# working.net
KiCad netlist of a schematic drawn in EAGLE
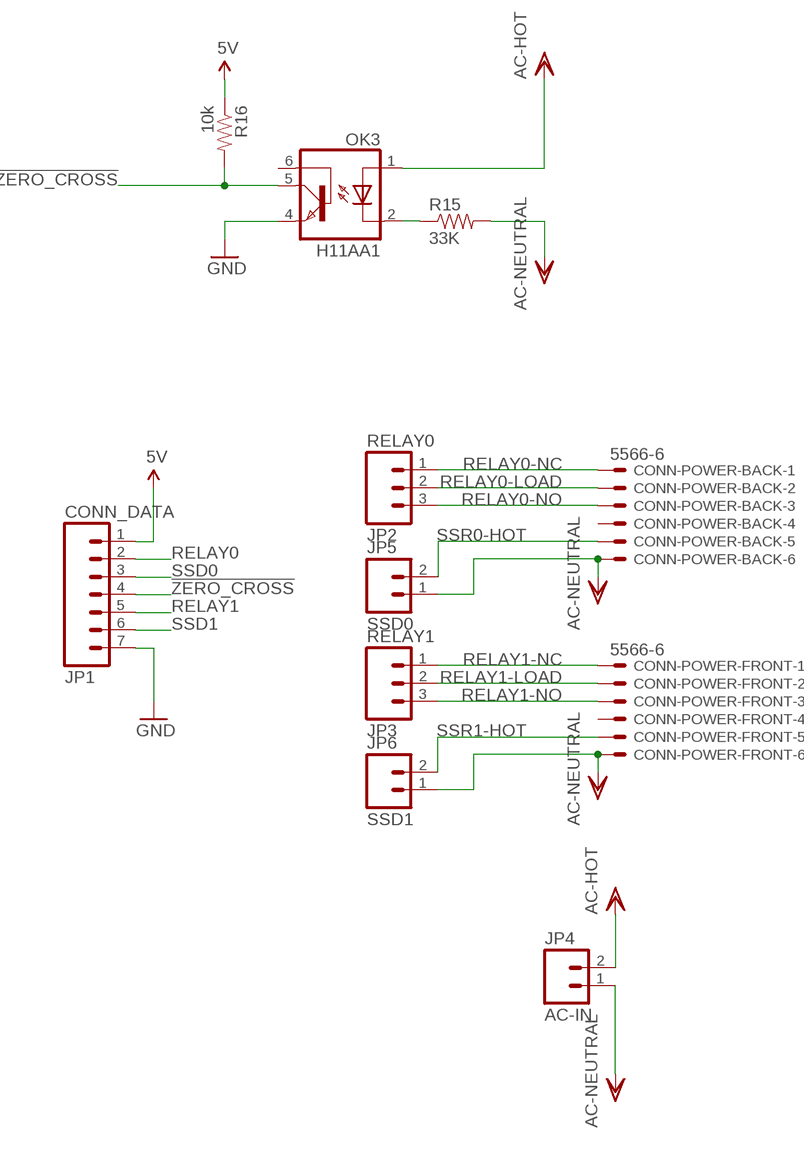
[diagram p0: schematic, sheet 1]
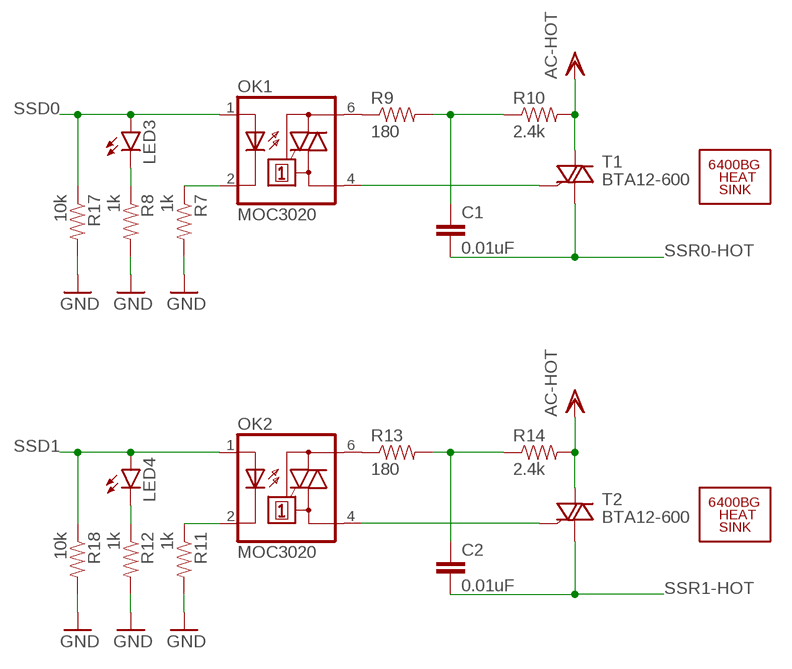
[diagram p1: schematic, sheet 2]
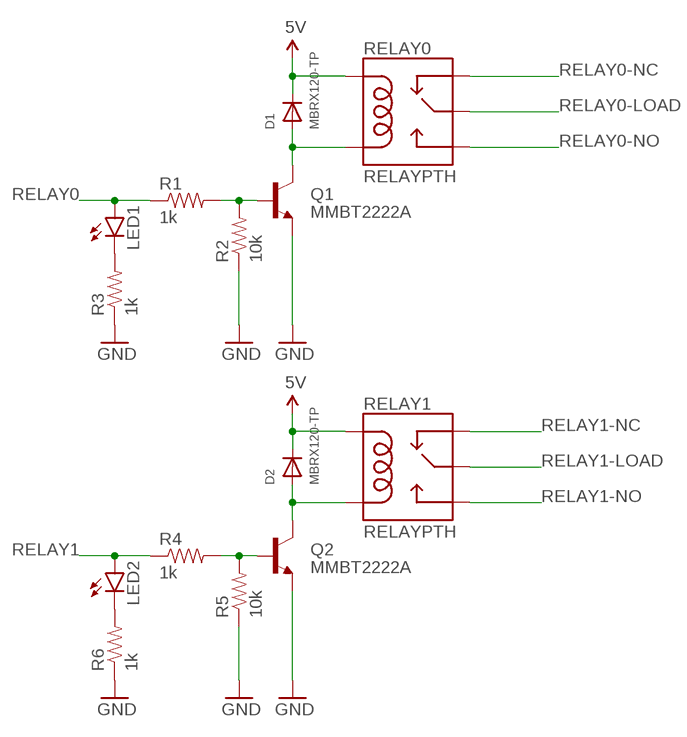
[diagram p2: schematic, sheet 3]

(export (version "E")
  (design (tool "Eeschema 10.0.6"))
  (components
    (comp (ref "D1")
      (value "MBRX120-TP")
      (footprint "eagle-import:SOD-123")
      (libsource (lib "eagle-import") (part "DIODESOD-123"))
    )
    (comp (ref "D2")
      (value "MBRX120-TP")
      (footprint "eagle-import:SOD-123")
      (libsource (lib "eagle-import") (part "DIODESOD-123"))
    )
    (comp (ref "LED1")
      (value "LED0603")
      (footprint "eagle-import:LED-0603")
      (libsource (lib "eagle-import") (part "LED0603"))
    )
    (comp (ref "LED2")
      (value "LED0603")
      (footprint "eagle-import:LED-0603")
      (libsource (lib "eagle-import") (part "LED0603"))
    )
    (comp (ref "Q1")
      (value "MMBT2222A")
      (footprint "eagle-import:SOT23-3")
      (libsource (lib "eagle-import") (part "TRANSISTOR_NPNMMBT2222A"))
    )
    (comp (ref "Q2")
      (value "MMBT2222A")
      (footprint "eagle-import:SOT23-3")
      (libsource (lib "eagle-import") (part "TRANSISTOR_NPNMMBT2222A"))
    )
    (comp (ref "R1")
      (value "1k")
      (footprint "eagle-import:0603-RES")
      (libsource (lib "eagle-import") (part "RESISTOR0603-RES"))
    )
    (comp (ref "R2")
      (value "10k")
      (footprint "eagle-import:0603-RES")
      (libsource (lib "eagle-import") (part "RESISTOR0603-RES"))
    )
    (comp (ref "R3")
      (value "1k")
      (footprint "eagle-import:0603-RES")
      (libsource (lib "eagle-import") (part "RESISTOR0603-RES"))
    )
    (comp (ref "R4")
      (value "1k")
      (footprint "eagle-import:0603-RES")
      (libsource (lib "eagle-import") (part "RESISTOR0603-RES"))
    )
    (comp (ref "R5")
      (value "10k")
      (footprint "eagle-import:0603-RES")
      (libsource (lib "eagle-import") (part "RESISTOR0603-RES"))
    )
    (comp (ref "R6")
      (value "1k")
      (footprint "eagle-import:0603-RES")
      (libsource (lib "eagle-import") (part "RESISTOR0603-RES"))
    )
    (comp (ref "RELAY0")
      (value "RELAYPTH")
      (footprint "eagle-import:RELAY-G5Q")
      (libsource (lib "eagle-import") (part "RELAYPTH"))
    )
    (comp (ref "RELAY1")
      (value "RELAYPTH")
      (footprint "eagle-import:RELAY-G5Q")
      (libsource (lib "eagle-import") (part "RELAYPTH"))
    )
    (comp (ref "CONN-POWER-BACK")
      (value "5566-6")
      (footprint "eagle-import:5566-6")
      (fields (field (name "MPN") "95566-61002"))
      (libsource (lib "eagle-import") (part "5566-6"))
    )
    (comp (ref "CONN-POWER-FRONT")
      (value "5566-6")
      (footprint "eagle-import:5566-6")
      (fields (field (name "MPN") "95566-61002"))
      (libsource (lib "eagle-import") (part "5566-6"))
    )
    (comp (ref "JP1")
      (value "CONN_DATA")
      (footprint "eagle-import:1X07_LONGPADS")
      (libsource (lib "eagle-import") (part "M07LONGPADS"))
    )
    (comp (ref "JP2")
      (value "RELAY0")
      (footprint "eagle-import:SCREWTERMINAL-5MM-3")
      (libsource (lib "eagle-import") (part "M03-SCREW-5MM"))
    )
    (comp (ref "JP3")
      (value "RELAY1")
      (footprint "eagle-import:SCREWTERMINAL-5MM-3")
      (libsource (lib "eagle-import") (part "M03-SCREW-5MM"))
    )
    (comp (ref "JP4")
      (value "AC-IN")
      (footprint "eagle-import:SCREWTERMINAL-5MM-2")
      (libsource (lib "eagle-import") (part "M025MM"))
    )
    (comp (ref "JP5")
      (value "SSD0")
      (footprint "eagle-import:SCREWTERMINAL-5MM-2")
      (libsource (lib "eagle-import") (part "M025MM"))
    )
    (comp (ref "JP6")
      (value "SSD1")
      (footprint "eagle-import:SCREWTERMINAL-5MM-2")
      (libsource (lib "eagle-import") (part "M025MM"))
    )
    (comp (ref "OK3")
      (value "H11AA1")
      (footprint "eagle-import:DIL6-SMD")
      (libsource (lib "eagle-import") (part "H11A?MS1"))
    )
    (comp (ref "R15")
      (value "33K")
      (footprint "eagle-import:0603-RES")
      (libsource (lib "eagle-import") (part "RESISTOR0603-RES"))
    )
    (comp (ref "R16")
      (value "10k")
      (footprint "eagle-import:0603-RES")
      (libsource (lib "eagle-import") (part "RESISTOR0603-RES"))
    )
    (comp (ref "C1")
      (value "0.01uF")
      (footprint "eagle-import:0603-CAP")
      (libsource (lib "eagle-import") (part "CAP0603-CAP"))
    )
    (comp (ref "C2")
      (value "0.01uF")
      (footprint "eagle-import:0603-CAP")
      (libsource (lib "eagle-import") (part "CAP0603-CAP"))
    )
    (comp (ref "LED3")
      (value "LED0603")
      (footprint "eagle-import:LED-0603")
      (libsource (lib "eagle-import") (part "LED0603"))
    )
    (comp (ref "LED4")
      (value "LED0603")
      (footprint "eagle-import:LED-0603")
      (libsource (lib "eagle-import") (part "LED0603"))
    )
    (comp (ref "OK1")
      (value "MOC3020")
      (footprint "eagle-import:DIL6-SMD")
      (fields (field (name "MF") "FAIRCHILD SEMICONDUCTOR") (field (name "MPN") "MOC3031SM"))
      (libsource (lib "eagle-import") (part "MOC30S31"))
    )
    (comp (ref "OK2")
      (value "MOC3020")
      (footprint "eagle-import:DIL6-SMD")
      (fields (field (name "MF") "FAIRCHILD SEMICONDUCTOR") (field (name "MPN") "MOC3031SM"))
      (libsource (lib "eagle-import") (part "MOC30S31"))
    )
    (comp (ref "R7")
      (value "1k")
      (footprint "eagle-import:0603-RES")
      (libsource (lib "eagle-import") (part "RESISTOR0603-RES"))
    )
    (comp (ref "R8")
      (value "1k")
      (footprint "eagle-import:0603-RES")
      (libsource (lib "eagle-import") (part "RESISTOR0603-RES"))
    )
    (comp (ref "R9")
      (value "180")
      (footprint "eagle-import:0603-RES")
      (libsource (lib "eagle-import") (part "RESISTOR0603-RES"))
    )
    (comp (ref "R10")
      (value "2.4k")
      (footprint "eagle-import:0603-RES")
      (libsource (lib "eagle-import") (part "RESISTOR0603-RES"))
    )
    (comp (ref "R11")
      (value "1k")
      (footprint "eagle-import:0603-RES")
      (libsource (lib "eagle-import") (part "RESISTOR0603-RES"))
    )
    (comp (ref "R12")
      (value "1k")
      (footprint "eagle-import:0603-RES")
      (libsource (lib "eagle-import") (part "RESISTOR0603-RES"))
    )
    (comp (ref "R13")
      (value "180")
      (footprint "eagle-import:0603-RES")
      (libsource (lib "eagle-import") (part "RESISTOR0603-RES"))
    )
    (comp (ref "R14")
      (value "2.4k")
      (footprint "eagle-import:0603-RES")
      (libsource (lib "eagle-import") (part "RESISTOR0603-RES"))
    )
    (comp (ref "R17")
      (value "10k")
      (footprint "eagle-import:0603-RES")
      (libsource (lib "eagle-import") (part "RESISTOR0603-RES"))
    )
    (comp (ref "R18")
      (value "10k")
      (footprint "eagle-import:0603-RES")
      (libsource (lib "eagle-import") (part "RESISTOR0603-RES"))
    )
    (comp (ref "T1")
      (value "BTA12-600")
      (footprint "eagle-import:TO220AB")
      (libsource (lib "eagle-import") (part "BT136"))
    )
    (comp (ref "T2")
      (value "BTA12-600")
      (footprint "eagle-import:TO220AB")
      (libsource (lib "eagle-import") (part "BT136"))
    )
    (comp (ref "U$3")
      (value "6400BG_HEATSINK")
      (footprint "eagle-import:6400BG_HEATSINK")
      (libsource (lib "eagle-import") (part "6400BG_HEATSINK"))
    )
    (comp (ref "U$4")
      (value "6400BG_HEATSINK")
      (footprint "eagle-import:6400BG_HEATSINK")
      (libsource (lib "eagle-import") (part "6400BG_HEATSINK"))
    )
  )
  (nets
    (net (code "1") (name "5V") (class "Default")
      (node (ref "D1") (pin "C") (pinfunction "C_C") (pintype "passive"))
      (node (ref "D2") (pin "C") (pinfunction "C_C") (pintype "passive"))
      (node (ref "JP1") (pin "1") (pinfunction "1_1") (pintype "passive"))
      (node (ref "R16") (pin "1") (pinfunction "1_1") (pintype "passive"))
      (node (ref "RELAY0") (pin "5") (pinfunction "COIL1_5") (pintype "bidirectional"))
      (node (ref "RELAY1") (pin "5") (pinfunction "COIL1_5") (pintype "bidirectional"))
    )
    (net (code "2") (name "AC-HOT") (class "Default")
      (node (ref "JP4") (pin "2") (pinfunction "2_2") (pintype "passive"))
      (node (ref "OK3") (pin "1") (pinfunction "A_1") (pintype "passive"))
      (node (ref "R10") (pin "2") (pinfunction "2_2") (pintype "passive"))
      (node (ref "R14") (pin "2") (pinfunction "2_2") (pintype "passive"))
      (node (ref "T1") (pin "2") (pinfunction "A2_2") (pintype "passive"))
      (node (ref "T2") (pin "2") (pinfunction "A2_2") (pintype "passive"))
    )
    (net (code "3") (name "AC-NEUTRAL") (class "Default")
      (node (ref "CONN-POWER-BACK") (pin "6") (pinfunction "S_6") (pintype "passive"))
      (node (ref "CONN-POWER-FRONT") (pin "6") (pinfunction "S_6") (pintype "passive"))
      (node (ref "JP4") (pin "1") (pinfunction "1_1") (pintype "passive"))
      (node (ref "JP5") (pin "1") (pinfunction "1_1") (pintype "passive"))
      (node (ref "JP6") (pin "1") (pinfunction "1_1") (pintype "passive"))
      (node (ref "R15") (pin "2") (pinfunction "2_2") (pintype "passive"))
    )
    (net (code "4") (name "GND") (class "Default")
      (node (ref "JP1") (pin "7") (pinfunction "7_7") (pintype "passive"))
      (node (ref "OK3") (pin "4") (pinfunction "EMI_4") (pintype "passive"))
      (node (ref "Q1") (pin "2") (pinfunction "E_2") (pintype "passive"))
      (node (ref "Q2") (pin "2") (pinfunction "E_2") (pintype "passive"))
      (node (ref "R11") (pin "2") (pinfunction "2_2") (pintype "passive"))
      (node (ref "R12") (pin "2") (pinfunction "2_2") (pintype "passive"))
      (node (ref "R17") (pin "2") (pinfunction "2_2") (pintype "passive"))
      (node (ref "R18") (pin "2") (pinfunction "2_2") (pintype "passive"))
      (node (ref "R2") (pin "1") (pinfunction "1_1") (pintype "passive"))
      (node (ref "R3") (pin "1") (pinfunction "1_1") (pintype "passive"))
      (node (ref "R5") (pin "1") (pinfunction "1_1") (pintype "passive"))
      (node (ref "R6") (pin "1") (pinfunction "1_1") (pintype "passive"))
      (node (ref "R7") (pin "2") (pinfunction "2_2") (pintype "passive"))
      (node (ref "R8") (pin "2") (pinfunction "2_2") (pintype "passive"))
    )
    (net (code "5") (name "Net-(C1-Pad1)") (class "Default")
      (node (ref "C1") (pin "1") (pinfunction "1_1") (pintype "passive"))
      (node (ref "R10") (pin "1") (pinfunction "1_1") (pintype "passive"))
      (node (ref "R9") (pin "2") (pinfunction "2_2") (pintype "passive"))
    )
    (net (code "6") (name "Net-(C2-Pad1)") (class "Default")
      (node (ref "C2") (pin "1") (pinfunction "1_1") (pintype "passive"))
      (node (ref "R13") (pin "2") (pinfunction "2_2") (pintype "passive"))
      (node (ref "R14") (pin "1") (pinfunction "1_1") (pintype "passive"))
    )
    (net (code "7") (name "Net-(LED1-PadC)") (class "Default")
      (node (ref "LED1") (pin "C") (pinfunction "C_C") (pintype "passive"))
      (node (ref "R3") (pin "2") (pinfunction "2_2") (pintype "passive"))
    )
    (net (code "8") (name "Net-(LED2-PadC)") (class "Default")
      (node (ref "LED2") (pin "C") (pinfunction "C_C") (pintype "passive"))
      (node (ref "R6") (pin "2") (pinfunction "2_2") (pintype "passive"))
    )
    (net (code "9") (name "Net-(LED3-PadC)") (class "Default")
      (node (ref "LED3") (pin "C") (pinfunction "C_C") (pintype "passive"))
      (node (ref "R8") (pin "1") (pinfunction "1_1") (pintype "passive"))
    )
    (net (code "10") (name "Net-(LED4-PadC)") (class "Default")
      (node (ref "LED4") (pin "C") (pinfunction "C_C") (pintype "passive"))
      (node (ref "R12") (pin "1") (pinfunction "1_1") (pintype "passive"))
    )
    (net (code "11") (name "Net-(OK1-A1)") (class "Default")
      (node (ref "OK1") (pin "4") (pinfunction "A1_4") (pintype "passive"))
      (node (ref "T1") (pin "3") (pinfunction "G_3") (pintype "passive"))
    )
    (net (code "12") (name "Net-(OK1-A2)") (class "Default")
      (node (ref "OK1") (pin "6") (pinfunction "A2_6") (pintype "passive"))
      (node (ref "R9") (pin "1") (pinfunction "1_1") (pintype "passive"))
    )
    (net (code "13") (name "Net-(OK1-C)") (class "Default")
      (node (ref "OK1") (pin "2") (pinfunction "C_2") (pintype "passive"))
      (node (ref "R7") (pin "1") (pinfunction "1_1") (pintype "passive"))
    )
    (net (code "14") (name "Net-(OK2-A1)") (class "Default")
      (node (ref "OK2") (pin "4") (pinfunction "A1_4") (pintype "passive"))
      (node (ref "T2") (pin "3") (pinfunction "G_3") (pintype "passive"))
    )
    (net (code "15") (name "Net-(OK2-A2)") (class "Default")
      (node (ref "OK2") (pin "6") (pinfunction "A2_6") (pintype "passive"))
      (node (ref "R13") (pin "1") (pinfunction "1_1") (pintype "passive"))
    )
    (net (code "16") (name "Net-(OK2-C)") (class "Default")
      (node (ref "OK2") (pin "2") (pinfunction "C_2") (pintype "passive"))
      (node (ref "R11") (pin "1") (pinfunction "1_1") (pintype "passive"))
    )
    (net (code "17") (name "Net-(OK3-C)") (class "Default")
      (node (ref "OK3") (pin "2") (pinfunction "C_2") (pintype "passive"))
      (node (ref "R15") (pin "1") (pinfunction "1_1") (pintype "passive"))
    )
    (net (code "18") (name "Net-(Q1-B)") (class "Default")
      (node (ref "Q1") (pin "1") (pinfunction "B_1") (pintype "passive"))
      (node (ref "R1") (pin "2") (pinfunction "2_2") (pintype "passive"))
      (node (ref "R2") (pin "2") (pinfunction "2_2") (pintype "passive"))
    )
    (net (code "19") (name "Net-(Q1-C)") (class "Default")
      (node (ref "D1") (pin "A") (pinfunction "A_A") (pintype "passive"))
      (node (ref "Q1") (pin "3") (pinfunction "C_3") (pintype "passive"))
      (node (ref "RELAY0") (pin "1") (pinfunction "COIL2_1") (pintype "bidirectional"))
    )
    (net (code "20") (name "Net-(Q2-B)") (class "Default")
      (node (ref "Q2") (pin "1") (pinfunction "B_1") (pintype "passive"))
      (node (ref "R4") (pin "2") (pinfunction "2_2") (pintype "passive"))
      (node (ref "R5") (pin "2") (pinfunction "2_2") (pintype "passive"))
    )
    (net (code "21") (name "Net-(Q2-C)") (class "Default")
      (node (ref "D2") (pin "A") (pinfunction "A_A") (pintype "passive"))
      (node (ref "Q2") (pin "3") (pinfunction "C_3") (pintype "passive"))
      (node (ref "RELAY1") (pin "1") (pinfunction "COIL2_1") (pintype "bidirectional"))
    )
    (net (code "22") (name "RELAY0") (class "Default")
      (node (ref "JP1") (pin "2") (pinfunction "2_2") (pintype "passive"))
      (node (ref "LED1") (pin "A") (pinfunction "A_A") (pintype "passive"))
      (node (ref "R1") (pin "1") (pinfunction "1_1") (pintype "passive"))
    )
    (net (code "23") (name "RELAY0-LOAD") (class "Default")
      (node (ref "CONN-POWER-BACK") (pin "2") (pinfunction "S_2") (pintype "passive"))
      (node (ref "JP2") (pin "2") (pinfunction "2_2") (pintype "passive"))
      (node (ref "RELAY0") (pin "2") (pinfunction "MAIN_2") (pintype "bidirectional"))
    )
    (net (code "24") (name "RELAY0-NC") (class "Default")
      (node (ref "CONN-POWER-BACK") (pin "1") (pinfunction "S_1") (pintype "passive"))
      (node (ref "JP2") (pin "1") (pinfunction "1_1") (pintype "passive"))
      (node (ref "RELAY0") (pin "4") (pinfunction "NC_4") (pintype "bidirectional"))
    )
    (net (code "25") (name "RELAY0-NO") (class "Default")
      (node (ref "CONN-POWER-BACK") (pin "3") (pinfunction "S_3") (pintype "passive"))
      (node (ref "JP2") (pin "3") (pinfunction "3_3") (pintype "passive"))
      (node (ref "RELAY0") (pin "3") (pinfunction "NO_3") (pintype "bidirectional"))
    )
    (net (code "26") (name "RELAY1") (class "Default")
      (node (ref "JP1") (pin "5") (pinfunction "5_5") (pintype "passive"))
      (node (ref "LED2") (pin "A") (pinfunction "A_A") (pintype "passive"))
      (node (ref "R4") (pin "1") (pinfunction "1_1") (pintype "passive"))
    )
    (net (code "27") (name "RELAY1-LOAD") (class "Default")
      (node (ref "CONN-POWER-FRONT") (pin "2") (pinfunction "S_2") (pintype "passive"))
      (node (ref "JP3") (pin "2") (pinfunction "2_2") (pintype "passive"))
      (node (ref "RELAY1") (pin "2") (pinfunction "MAIN_2") (pintype "bidirectional"))
    )
    (net (code "28") (name "RELAY1-NC") (class "Default")
      (node (ref "CONN-POWER-FRONT") (pin "1") (pinfunction "S_1") (pintype "passive"))
      (node (ref "JP3") (pin "1") (pinfunction "1_1") (pintype "passive"))
      (node (ref "RELAY1") (pin "4") (pinfunction "NC_4") (pintype "bidirectional"))
    )
    (net (code "29") (name "RELAY1-NO") (class "Default")
      (node (ref "CONN-POWER-FRONT") (pin "3") (pinfunction "S_3") (pintype "passive"))
      (node (ref "JP3") (pin "3") (pinfunction "3_3") (pintype "passive"))
      (node (ref "RELAY1") (pin "3") (pinfunction "NO_3") (pintype "bidirectional"))
    )
    (net (code "30") (name "SSD0") (class "Default")
      (node (ref "JP1") (pin "3") (pinfunction "3_3") (pintype "passive"))
      (node (ref "LED3") (pin "A") (pinfunction "A_A") (pintype "passive"))
      (node (ref "OK1") (pin "1") (pinfunction "A_1") (pintype "passive"))
      (node (ref "R17") (pin "1") (pinfunction "1_1") (pintype "passive"))
    )
    (net (code "31") (name "SSD1") (class "Default")
      (node (ref "JP1") (pin "6") (pinfunction "6_6") (pintype "passive"))
      (node (ref "LED4") (pin "A") (pinfunction "A_A") (pintype "passive"))
      (node (ref "OK2") (pin "1") (pinfunction "A_1") (pintype "passive"))
      (node (ref "R18") (pin "1") (pinfunction "1_1") (pintype "passive"))
    )
    (net (code "32") (name "SSR0-HOT") (class "Default")
      (node (ref "C1") (pin "2") (pinfunction "2_2") (pintype "passive"))
      (node (ref "CONN-POWER-BACK") (pin "5") (pinfunction "S_5") (pintype "passive"))
      (node (ref "JP5") (pin "2") (pinfunction "2_2") (pintype "passive"))
      (node (ref "T1") (pin "1") (pinfunction "A1_1") (pintype "passive"))
    )
    (net (code "33") (name "SSR1-HOT") (class "Default")
      (node (ref "C2") (pin "2") (pinfunction "2_2") (pintype "passive"))
      (node (ref "CONN-POWER-FRONT") (pin "5") (pinfunction "S_5") (pintype "passive"))
      (node (ref "JP6") (pin "2") (pinfunction "2_2") (pintype "passive"))
      (node (ref "T2") (pin "1") (pinfunction "A1_1") (pintype "passive"))
    )
    (net (code "34") (name "unconnected-(CONN-POWER-BACKD-S-Pad4)") (class "Default")
      (node (ref "CONN-POWER-BACK") (pin "4") (pinfunction "S_4") (pintype "passive"))
    )
    (net (code "35") (name "unconnected-(CONN-POWER-FRONTD-S-Pad4)") (class "Default")
      (node (ref "CONN-POWER-FRONT") (pin "4") (pinfunction "S_4") (pintype "passive"))
    )
    (net (code "36") (name "unconnected-(OK3-BAS-Pad6)") (class "Default")
      (node (ref "OK3") (pin "6") (pinfunction "BAS_6") (pintype "passive"))
    )
    (net (code "37") (name "~{ZERO_CROSS}") (class "Default")
      (node (ref "JP1") (pin "4") (pinfunction "4_4") (pintype "passive"))
      (node (ref "OK3") (pin "5") (pinfunction "COL_5") (pintype "passive"))
      (node (ref "R16") (pin "2") (pinfunction "2_2") (pintype "passive"))
    )
  )
)
